# KGGR_UCCv2.net
KiCad netlist of a schematic drawn in EAGLE
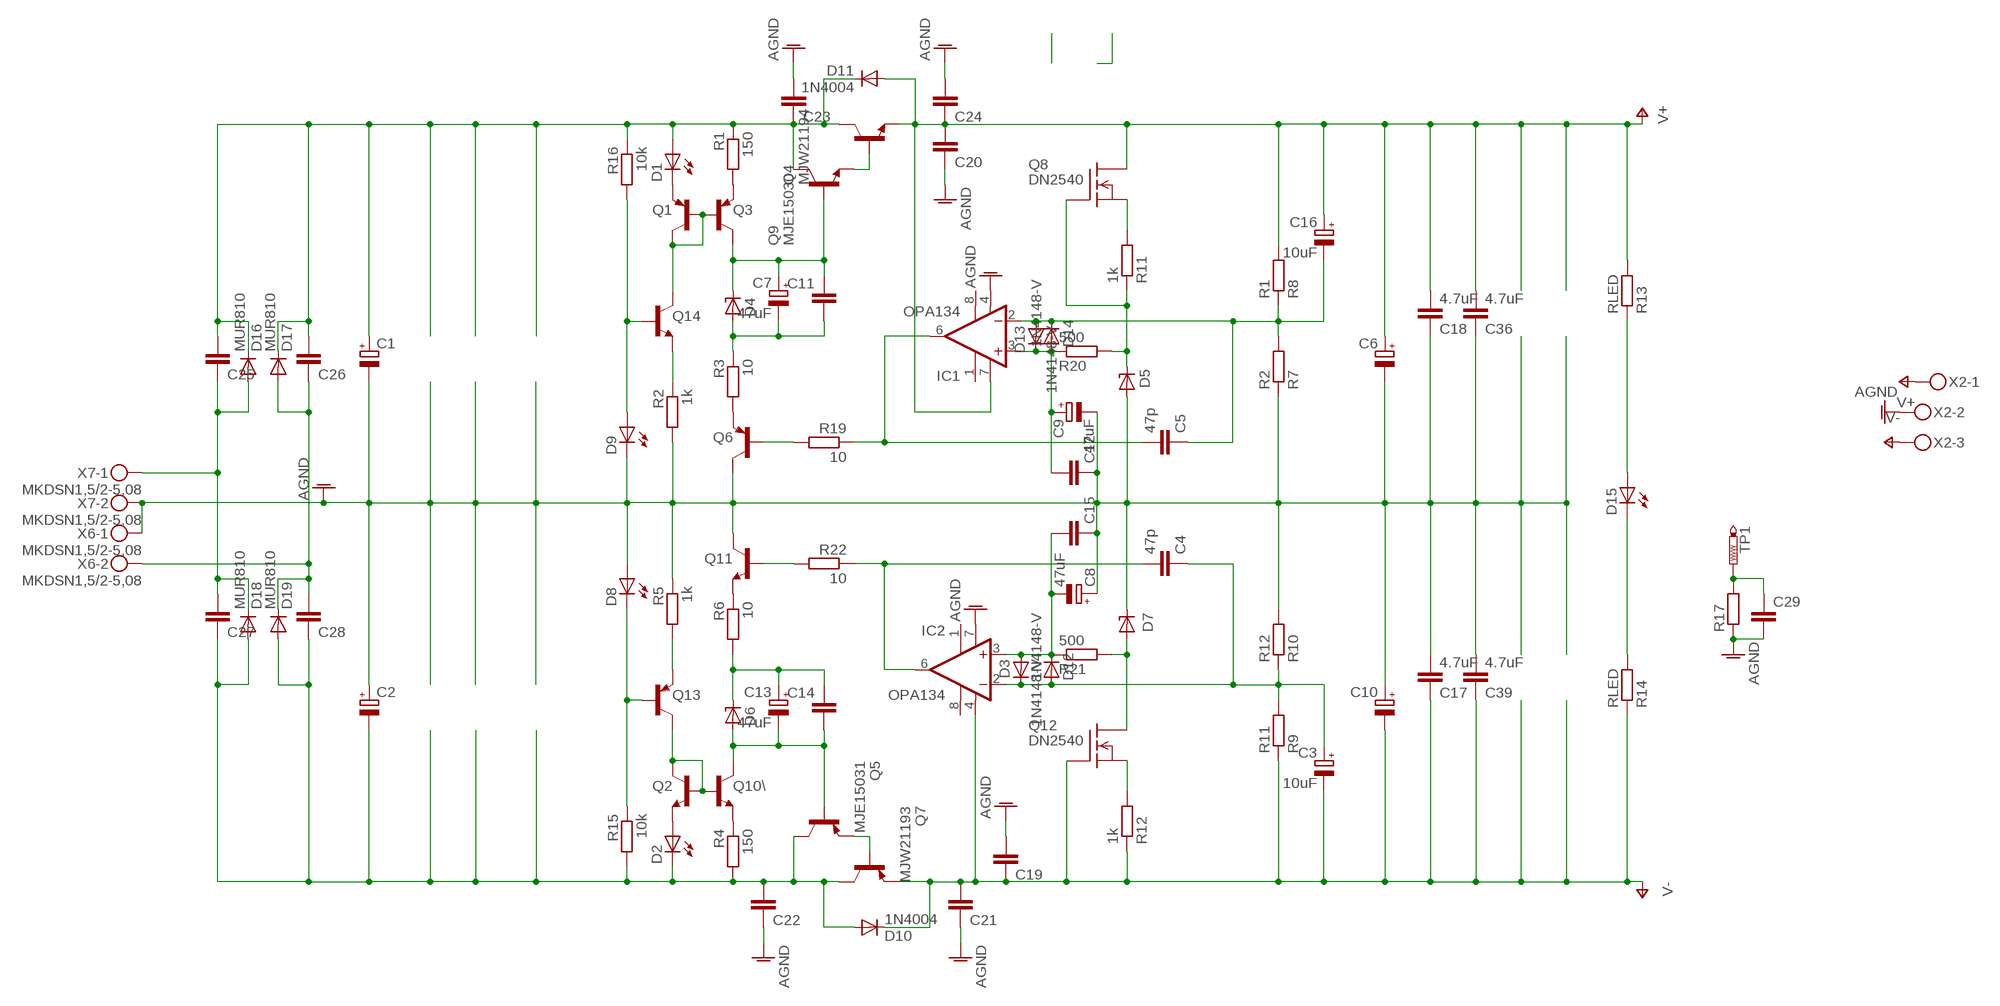
[diagram p0: schematic, sheet 1]

(export (version "E")
  (design (tool "Eeschema 10.0.6"))
  (components
    (comp (ref "C1")
      (value "CPOL-EUE10-30")
      (footprint "eagle-import:EB30D")
      (libsource (lib "eagle-import") (part "CPOL-EUE10-30"))
    )
    (comp (ref "C2")
      (value "CPOL-EUE10-30")
      (footprint "eagle-import:EB30D")
      (libsource (lib "eagle-import") (part "CPOL-EUE10-30"))
    )
    (comp (ref "C3")
      (value "10uF")
      (footprint "eagle-import:SP-CAP-CX")
      (libsource (lib "eagle-import") (part "CPOL-EUSP-CAP-CX"))
    )
    (comp (ref "C4")
      (value "47p")
      (footprint "eagle-import:C1206")
      (libsource (lib "eagle-import") (part "C-EUC1206"))
    )
    (comp (ref "C5")
      (value "47p")
      (footprint "eagle-import:C1206")
      (libsource (lib "eagle-import") (part "C-EUC1206"))
    )
    (comp (ref "C6")
      (value "CPOL-EUE5-13")
      (footprint "eagle-import:E5-13")
      (libsource (lib "eagle-import") (part "CPOL-EUE5-13"))
    )
    (comp (ref "C7")
      (value "47uF")
      (footprint "eagle-import:SP-CAP-CX")
      (libsource (lib "eagle-import") (part "CPOL-EUSP-CAP-CX"))
    )
    (comp (ref "C8")
      (value "47uF")
      (footprint "eagle-import:SP-CAP-CX")
      (libsource (lib "eagle-import") (part "CPOL-EUSP-CAP-CX"))
    )
    (comp (ref "C9")
      (value "47uF")
      (footprint "eagle-import:SP-CAP-CX")
      (libsource (lib "eagle-import") (part "CPOL-EUSP-CAP-CX"))
    )
    (comp (ref "C10")
      (value "CPOL-EUE5-13")
      (footprint "eagle-import:E5-13")
      (libsource (lib "eagle-import") (part "CPOL-EUE5-13"))
    )
    (comp (ref "C11")
      (value "C-EUC1206")
      (footprint "eagle-import:C1206")
      (libsource (lib "eagle-import") (part "C-EUC1206"))
    )
    (comp (ref "C12")
      (value "C-EU050-035X075")
      (footprint "eagle-import:C050-035X075")
      (libsource (lib "eagle-import") (part "C-EU050-035X075"))
    )
    (comp (ref "C13")
      (value "47uF")
      (footprint "eagle-import:SP-CAP-CX")
      (libsource (lib "eagle-import") (part "CPOL-EUSP-CAP-CX"))
    )
    (comp (ref "C14")
      (value "C-EUC1206")
      (footprint "eagle-import:C1206")
      (libsource (lib "eagle-import") (part "C-EUC1206"))
    )
    (comp (ref "C15")
      (value "C-EU050-035X075")
      (footprint "eagle-import:C050-035X075")
      (libsource (lib "eagle-import") (part "C-EU050-035X075"))
    )
    (comp (ref "C16")
      (value "10uF")
      (footprint "eagle-import:SP-CAP-CX")
      (libsource (lib "eagle-import") (part "CPOL-EUSP-CAP-CX"))
    )
    (comp (ref "C17")
      (value "4.7uF")
      (footprint "eagle-import:C1206")
      (libsource (lib "eagle-import") (part "C-EUC1206"))
    )
    (comp (ref "C18")
      (value "4.7uF")
      (footprint "eagle-import:C1206")
      (libsource (lib "eagle-import") (part "C-EUC1206"))
    )
    (comp (ref "C19")
      (value "C-EU050-035X075")
      (footprint "eagle-import:C050-035X075")
      (libsource (lib "eagle-import") (part "C-EU050-035X075"))
    )
    (comp (ref "C20")
      (value "C-EU050-035X075")
      (footprint "eagle-import:C050-035X075")
      (libsource (lib "eagle-import") (part "C-EU050-035X075"))
    )
    (comp (ref "C21")
      (value "C-EU050-035X075")
      (footprint "eagle-import:C050-035X075")
      (libsource (lib "eagle-import") (part "C-EU050-035X075"))
    )
    (comp (ref "C22")
      (value "C-EU050-075X075")
      (footprint "eagle-import:C050-075X075")
      (libsource (lib "eagle-import") (part "C-EU050-075X075"))
    )
    (comp (ref "C23")
      (value "C-EU050-075X075")
      (footprint "eagle-import:C050-075X075")
      (libsource (lib "eagle-import") (part "C-EU050-075X075"))
    )
    (comp (ref "C24")
      (value "C-EU050-035X075")
      (footprint "eagle-import:C050-035X075")
      (libsource (lib "eagle-import") (part "C-EU050-035X075"))
    )
    (comp (ref "C25")
      (value "C-EU050-035X075")
      (footprint "eagle-import:C050-035X075")
      (libsource (lib "eagle-import") (part "C-EU050-035X075"))
    )
    (comp (ref "C26")
      (value "C-EU050-035X075")
      (footprint "eagle-import:C050-035X075")
      (libsource (lib "eagle-import") (part "C-EU050-035X075"))
    )
    (comp (ref "C27")
      (value "C-EU050-035X075")
      (footprint "eagle-import:C050-035X075")
      (libsource (lib "eagle-import") (part "C-EU050-035X075"))
    )
    (comp (ref "C28")
      (value "C-EU050-035X075")
      (footprint "eagle-import:C050-035X075")
      (libsource (lib "eagle-import") (part "C-EU050-035X075"))
    )
    (comp (ref "C29")
      (value "C-EU075-042X103")
      (footprint "eagle-import:C075-042X103")
      (libsource (lib "eagle-import") (part "C-EU075-042X103"))
    )
    (comp (ref "C36")
      (value "4.7uF")
      (footprint "eagle-import:C1206")
      (libsource (lib "eagle-import") (part "C-EUC1206"))
    )
    (comp (ref "C39")
      (value "4.7uF")
      (footprint "eagle-import:C1206")
      (libsource (lib "eagle-import") (part "C-EUC1206"))
    )
    (comp (ref "D1")
      (value "LED5MM")
      (footprint "eagle-import:LED5MM")
      (libsource (lib "eagle-import") (part "LED5MM"))
    )
    (comp (ref "D2")
      (value "LED5MM")
      (footprint "eagle-import:LED5MM")
      (libsource (lib "eagle-import") (part "LED5MM"))
    )
    (comp (ref "D3")
      (value "1N4148-V")
      (footprint "eagle-import:1N4148")
      (libsource (lib "eagle-import") (part "1N4148-V"))
    )
    (comp (ref "D4")
      (value "1N4728")
      (footprint "eagle-import:DO41Z10")
      (libsource (lib "eagle-import") (part "1N4728"))
    )
    (comp (ref "D5")
      (value "LT1021")
      (footprint "eagle-import:DIL08")
      (libsource (lib "eagle-import") (part "LT1021-V"))
    )
    (comp (ref "D6")
      (value "1N4728")
      (footprint "eagle-import:DO41Z10")
      (libsource (lib "eagle-import") (part "1N4728"))
    )
    (comp (ref "D7")
      (value "LT1021")
      (footprint "eagle-import:DIL08")
      (libsource (lib "eagle-import") (part "LT1021-V"))
    )
    (comp (ref "D8")
      (value "LED5MM")
      (footprint "eagle-import:LED5MM")
      (libsource (lib "eagle-import") (part "LED5MM"))
    )
    (comp (ref "D9")
      (value "LED5MM")
      (footprint "eagle-import:LED5MM")
      (libsource (lib "eagle-import") (part "LED5MM"))
    )
    (comp (ref "D10")
      (value "1N4004")
      (footprint "eagle-import:DO41-10")
      (libsource (lib "eagle-import") (part "diode_210_1N4004"))
    )
    (comp (ref "D11")
      (value "1N4004")
      (footprint "eagle-import:DO41-10")
      (libsource (lib "eagle-import") (part "1N4004"))
    )
    (comp (ref "D12")
      (value "1N4148-V")
      (footprint "eagle-import:1N4148")
      (libsource (lib "eagle-import") (part "1N4148-V"))
    )
    (comp (ref "D13")
      (value "1N4148-V")
      (footprint "eagle-import:1N4148")
      (libsource (lib "eagle-import") (part "1N4148-V"))
    )
    (comp (ref "D14")
      (value "1N4148-V")
      (footprint "eagle-import:1N4148")
      (libsource (lib "eagle-import") (part "1N4148-V"))
    )
    (comp (ref "D15")
      (value "LED5MM")
      (footprint "eagle-import:LED5MM")
      (libsource (lib "eagle-import") (part "LED5MM"))
    )
    (comp (ref "D16")
      (value "MUR810")
      (footprint "eagle-import:TO220ACS")
      (libsource (lib "eagle-import") (part "MUR810"))
    )
    (comp (ref "D17")
      (value "MUR810")
      (footprint "eagle-import:TO220ACS")
      (libsource (lib "eagle-import") (part "MUR810"))
    )
    (comp (ref "D18")
      (value "MUR810")
      (footprint "eagle-import:TO220ACS")
      (libsource (lib "eagle-import") (part "MUR810"))
    )
    (comp (ref "D19")
      (value "MUR810")
      (footprint "eagle-import:TO220ACS")
      (libsource (lib "eagle-import") (part "MUR810"))
    )
    (comp (ref "IC1")
      (value "OPA134")
      (footprint "eagle-import:DIL08")
      (fields (field (name "MF") "TEXAS INSTRUMENTS") (field (name "MPN") "OPA134PA"))
      (libsource (lib "eagle-import") (part "OPA134P"))
    )
    (comp (ref "IC2")
      (value "OPA134")
      (footprint "eagle-import:DIL08")
      (fields (field (name "MF") "TEXAS INSTRUMENTS") (field (name "MPN") "OPA134PA"))
      (libsource (lib "eagle-import") (part "OPA134P"))
    )
    (comp (ref "Q1")
      (value "MPSA92-PNP-TO92-EBC")
      (footprint "eagle-import:TO92-EBC")
      (libsource (lib "eagle-import") (part "-PNP-TO92-EBCMPSA92"))
    )
    (comp (ref "Q2")
      (value "MPSA42-NPN-TO92-EBC")
      (footprint "eagle-import:TO92-EBC")
      (libsource (lib "eagle-import") (part "-NPN-TO92-EBCMPSA42"))
    )
    (comp (ref "Q3")
      (value "MPSA92-PNP-TO92-EBC")
      (footprint "eagle-import:TO92-EBC")
      (libsource (lib "eagle-import") (part "-PNP-TO92-EBCMPSA92"))
    )
    (comp (ref "Q4")
      (value "MJW21194")
      (footprint "eagle-import:TO-264")
      (libsource (lib "eagle-import") (part "MJL4281"))
    )
    (comp (ref "Q5")
      (value "MJE15031")
      (footprint "eagle-import:TO220KG")
      (libsource (lib "eagle-import") (part "MJE15031"))
    )
    (comp (ref "Q6")
      (value "MPSA92-PNP-TO92-EBC")
      (footprint "eagle-import:TO92-EBC")
      (libsource (lib "eagle-import") (part "-PNP-TO92-EBCMPSA92"))
    )
    (comp (ref "Q7")
      (value "MJW21193")
      (footprint "eagle-import:TO-264")
      (libsource (lib "eagle-import") (part "MJL4302"))
    )
    (comp (ref "Q8")
      (value "DN2540")
      (footprint "eagle-import:TO92-")
      (libsource (lib "eagle-import") (part "2N7000TO92"))
    )
    (comp (ref "Q9")
      (value "MJE15030")
      (footprint "eagle-import:TO220KG")
      (libsource (lib "eagle-import") (part "MJE15030"))
    )
    (comp (ref "Q10\\")
      (value "MPSA42-NPN-TO92-EBC")
      (footprint "eagle-import:TO92-EBC")
      (libsource (lib "eagle-import") (part "-NPN-TO92-EBCMPSA42"))
    )
    (comp (ref "Q11")
      (value "MPSA42-NPN-TO92-EBC")
      (footprint "eagle-import:TO92-EBC")
      (libsource (lib "eagle-import") (part "-NPN-TO92-EBCMPSA42"))
    )
    (comp (ref "Q12")
      (value "DN2540")
      (footprint "eagle-import:TO92-")
      (libsource (lib "eagle-import") (part "2N7000TO92"))
    )
    (comp (ref "Q13")
      (value "MPSA92-PNP-TO92-EBC")
      (footprint "eagle-import:TO92-EBC")
      (libsource (lib "eagle-import") (part "-PNP-TO92-EBCMPSA92"))
    )
    (comp (ref "Q14")
      (value "MPSA42-NPN-TO92-EBC")
      (footprint "eagle-import:TO92-EBC")
      (libsource (lib "eagle-import") (part "-NPN-TO92-EBCMPSA42"))
    )
    (comp (ref "R1")
      (value "150")
      (footprint "eagle-import:0207_2V")
      (libsource (lib "eagle-import") (part "R-EU_0207/2V"))
    )
    (comp (ref "R2")
      (value "1k")
      (footprint "eagle-import:0207_2V")
      (libsource (lib "eagle-import") (part "R-EU_0207/2V"))
    )
    (comp (ref "R3")
      (value "10")
      (footprint "eagle-import:0207_2V")
      (libsource (lib "eagle-import") (part "R-EU_0207/2V"))
    )
    (comp (ref "R4")
      (value "150")
      (footprint "eagle-import:0207_2V")
      (libsource (lib "eagle-import") (part "R-EU_0207/2V"))
    )
    (comp (ref "R5")
      (value "1k")
      (footprint "eagle-import:0207_2V")
      (libsource (lib "eagle-import") (part "R-EU_0207/2V"))
    )
    (comp (ref "R6")
      (value "10")
      (footprint "eagle-import:0207_2V")
      (libsource (lib "eagle-import") (part "R-EU_0207/2V"))
    )
    (comp (ref "R7")
      (value "R2")
      (footprint "eagle-import:0207_2V")
      (libsource (lib "eagle-import") (part "R-EU_0207/2V"))
    )
    (comp (ref "R8")
      (value "R1")
      (footprint "eagle-import:0207_2V")
      (libsource (lib "eagle-import") (part "R-EU_0207/2V"))
    )
    (comp (ref "R9")
      (value "R11")
      (footprint "eagle-import:0207_2V")
      (libsource (lib "eagle-import") (part "R-EU_0207/2V"))
    )
    (comp (ref "R10")
      (value "R12")
      (footprint "eagle-import:0207_2V")
      (libsource (lib "eagle-import") (part "R-EU_0207/2V"))
    )
    (comp (ref "R11")
      (value "1k")
      (footprint "eagle-import:0207_2V")
      (libsource (lib "eagle-import") (part "R-EU_0207/2V"))
    )
    (comp (ref "R12")
      (value "1k")
      (footprint "eagle-import:0207_2V")
      (libsource (lib "eagle-import") (part "R-EU_0207/2V"))
    )
    (comp (ref "R13")
      (value "RLED")
      (footprint "eagle-import:0207_2V")
      (libsource (lib "eagle-import") (part "R-EU_0207/2V"))
    )
    (comp (ref "R14")
      (value "RLED")
      (footprint "eagle-import:0207_2V")
      (libsource (lib "eagle-import") (part "R-EU_0207/2V"))
    )
    (comp (ref "R15")
      (value "10k")
      (footprint "eagle-import:0207_2V")
      (libsource (lib "eagle-import") (part "R-EU_0207/2V"))
    )
    (comp (ref "R16")
      (value "10k")
      (footprint "eagle-import:0207_2V")
      (libsource (lib "eagle-import") (part "R-EU_0207/2V"))
    )
    (comp (ref "R17")
      (value "R-EU_0207/10")
      (footprint "eagle-import:0207_10")
      (libsource (lib "eagle-import") (part "R-EU_0207/10"))
    )
    (comp (ref "R19")
      (value "10")
      (footprint "eagle-import:0207_2V")
      (libsource (lib "eagle-import") (part "R-EU_0207/2V"))
    )
    (comp (ref "R20")
      (value "500")
      (footprint "eagle-import:0207_2V")
      (libsource (lib "eagle-import") (part "R-EU_0207/2V"))
    )
    (comp (ref "R21")
      (value "500")
      (footprint "eagle-import:0207_2V")
      (libsource (lib "eagle-import") (part "R-EU_0207/2V"))
    )
    (comp (ref "R22")
      (value "10")
      (footprint "eagle-import:0207_2V")
      (libsource (lib "eagle-import") (part "R-EU_0207/2V"))
    )
    (comp (ref "TP1")
      (value "PTR1PAD1-20")
      (footprint "eagle-import:P1-20")
      (libsource (lib "eagle-import") (part "PTR1PAD1-20"))
    )
    (comp (ref "X2")
      (value "MKDSN1,5/3-5,08")
      (footprint "eagle-import:MKDSN1,5_3-5,08")
      (libsource (lib "eagle-import") (part "MKDSN1,5/3-5,08"))
    )
    (comp (ref "X6")
      (value "MKDSN1,5/2-5,08")
      (footprint "eagle-import:MKDSN1,5_2-5,08")
      (libsource (lib "eagle-import") (part "MKDSN1,5/2-5,08"))
    )
    (comp (ref "X7")
      (value "MKDSN1,5/2-5,08")
      (footprint "eagle-import:MKDSN1,5_2-5,08")
      (libsource (lib "eagle-import") (part "MKDSN1,5/2-5,08"))
    )
  )
  (nets
    (net (code "1") (name "AGND") (class "Default")
      (node (ref "C1") (pin "-") (pinfunction "-_-") (pintype "passive"))
      (node (ref "C10") (pin "+") (pinfunction "+_+") (pintype "passive"))
      (node (ref "C12") (pin "1") (pinfunction "1_1") (pintype "passive"))
      (node (ref "C15") (pin "1") (pinfunction "1_1") (pintype "passive"))
      (node (ref "C17") (pin "2") (pinfunction "2_2") (pintype "passive"))
      (node (ref "C18") (pin "1") (pinfunction "1_1") (pintype "passive"))
      (node (ref "C19") (pin "2") (pinfunction "2_2") (pintype "passive"))
      (node (ref "C2") (pin "+") (pinfunction "+_+") (pintype "passive"))
      (node (ref "C20") (pin "1") (pinfunction "1_1") (pintype "passive"))
      (node (ref "C21") (pin "1") (pinfunction "1_1") (pintype "passive"))
      (node (ref "C22") (pin "1") (pinfunction "1_1") (pintype "passive"))
      (node (ref "C23") (pin "2") (pinfunction "2_2") (pintype "passive"))
      (node (ref "C24") (pin "2") (pinfunction "2_2") (pintype "passive"))
      (node (ref "C29") (pin "2") (pinfunction "2_2") (pintype "passive"))
      (node (ref "C36") (pin "1") (pinfunction "1_1") (pintype "passive"))
      (node (ref "C39") (pin "2") (pinfunction "2_2") (pintype "passive"))
      (node (ref "C6") (pin "-") (pinfunction "-_-") (pintype "passive"))
      (node (ref "C8") (pin "+") (pinfunction "+_+") (pintype "passive"))
      (node (ref "C9") (pin "-") (pinfunction "-_-") (pintype "passive"))
      (node (ref "D5") (pin "4") (pinfunction "GND_4") (pintype "passive"))
      (node (ref "D7") (pin "6") (pinfunction "OUT_6") (pintype "passive"))
      (node (ref "D8") (pin "A") (pinfunction "A_A") (pintype "passive"))
      (node (ref "D9") (pin "K") (pinfunction "C_K") (pintype "passive"))
      (node (ref "IC1") (pin "4") (pinfunction "V-_4") (pintype "power_in"))
      (node (ref "IC2") (pin "7") (pinfunction "V+_7") (pintype "power_in"))
      (node (ref "Q11") (pin "C") (pinfunction "C_C") (pintype "passive"))
      (node (ref "Q6") (pin "C") (pinfunction "C_C") (pintype "passive"))
      (node (ref "R10") (pin "2") (pinfunction "2_2") (pintype "passive"))
      (node (ref "R17") (pin "1") (pinfunction "1_1") (pintype "passive"))
      (node (ref "R2") (pin "2") (pinfunction "2_2") (pintype "passive"))
      (node (ref "R5") (pin "1") (pinfunction "1_1") (pintype "passive"))
      (node (ref "R7") (pin "1") (pinfunction "1_1") (pintype "passive"))
      (node (ref "X2") (pin "2") (pinfunction "KL_2") (pintype "passive"))
      (node (ref "X6") (pin "1") (pinfunction "KL_1") (pintype "passive"))
      (node (ref "X7") (pin "2") (pinfunction "KL_2") (pintype "passive"))
    )
    (net (code "2") (name "Net-(C11-Pad2)") (class "Default")
      (node (ref "C11") (pin "2") (pinfunction "2_2") (pintype "passive"))
      (node (ref "C7") (pin "-") (pinfunction "-_-") (pintype "passive"))
      (node (ref "D4") (pin "A") (pinfunction "A_A") (pintype "passive"))
      (node (ref "R3") (pin "1") (pinfunction "1_1") (pintype "passive"))
    )
    (net (code "3") (name "Net-(C13-Pad+)") (class "Default")
      (node (ref "C13") (pin "+") (pinfunction "+_+") (pintype "passive"))
      (node (ref "C14") (pin "1") (pinfunction "1_1") (pintype "passive"))
      (node (ref "D6") (pin "C") (pinfunction "C_C") (pintype "passive"))
      (node (ref "R6") (pin "2") (pinfunction "2_2") (pintype "passive"))
    )
    (net (code "4") (name "Net-(C29-Pad1)") (class "Default")
      (node (ref "C29") (pin "1") (pinfunction "1_1") (pintype "passive"))
      (node (ref "R17") (pin "2") (pinfunction "2_2") (pintype "passive"))
      (node (ref "TP1") (pin "TP") (pinfunction "TP_TP") (pintype "input"))
    )
    (net (code "5") (name "Net-(D1-C)") (class "Default")
      (node (ref "D1") (pin "K") (pinfunction "C_K") (pintype "passive"))
      (node (ref "Q1") (pin "E") (pinfunction "E_E") (pintype "passive"))
    )
    (net (code "6") (name "Net-(D2-C)") (class "Default")
      (node (ref "C2") (pin "-") (pinfunction "-_-") (pintype "passive"))
      (node (ref "C22") (pin "2") (pinfunction "2_2") (pintype "passive"))
      (node (ref "C27") (pin "1") (pinfunction "1_1") (pintype "passive"))
      (node (ref "C28") (pin "1") (pinfunction "1_1") (pintype "passive"))
      (node (ref "D10") (pin "A") (pinfunction "A_A") (pintype "passive"))
      (node (ref "D18") (pin "A") (pinfunction "A_A") (pintype "passive"))
      (node (ref "D19") (pin "A") (pinfunction "A_A") (pintype "passive"))
      (node (ref "D2") (pin "K") (pinfunction "C_K") (pintype "passive"))
      (node (ref "Q5") (pin "2") (pinfunction "C_2") (pintype "passive"))
      (node (ref "Q7") (pin "C") (pinfunction "C_C") (pintype "passive"))
      (node (ref "R15") (pin "2") (pinfunction "2_2") (pintype "passive"))
      (node (ref "R4") (pin "2") (pinfunction "2_2") (pintype "passive"))
    )
    (net (code "7") (name "Net-(D2-PadA)") (class "Default")
      (node (ref "D2") (pin "A") (pinfunction "A_A") (pintype "passive"))
      (node (ref "Q2") (pin "E") (pinfunction "E_E") (pintype "passive"))
    )
    (net (code "8") (name "Net-(D5-OUT)") (class "Default")
      (node (ref "D5") (pin "6") (pinfunction "OUT_6") (pintype "passive"))
      (node (ref "Q8") (pin "2") (pinfunction "G_2") (pintype "passive"))
      (node (ref "R11") (pin "1") (pinfunction "1_1") (pintype "passive"))
      (node (ref "R20") (pin "2") (pinfunction "2_2") (pintype "passive"))
    )
    (net (code "9") (name "Net-(D7-GND)") (class "Default")
      (node (ref "D7") (pin "4") (pinfunction "GND_4") (pintype "passive"))
      (node (ref "Q12") (pin "1") (pinfunction "D_1") (pintype "passive"))
      (node (ref "R21") (pin "2") (pinfunction "2_2") (pintype "passive"))
    )
    (net (code "10") (name "Net-(D8-C)") (class "Default")
      (node (ref "D8") (pin "K") (pinfunction "C_K") (pintype "passive"))
      (node (ref "Q13") (pin "B") (pinfunction "B_B") (pintype "passive"))
      (node (ref "R15") (pin "1") (pinfunction "1_1") (pintype "passive"))
    )
    (net (code "11") (name "Net-(D9-PadA)") (class "Default")
      (node (ref "D9") (pin "A") (pinfunction "A_A") (pintype "passive"))
      (node (ref "Q14") (pin "B") (pinfunction "B_B") (pintype "passive"))
      (node (ref "R16") (pin "2") (pinfunction "2_2") (pintype "passive"))
    )
    (net (code "12") (name "Net-(D15-C)") (class "Default")
      (node (ref "D15") (pin "K") (pinfunction "C_K") (pintype "passive"))
      (node (ref "R14") (pin "2") (pinfunction "2_2") (pintype "passive"))
    )
    (net (code "13") (name "Net-(D15-PadA)") (class "Default")
      (node (ref "D15") (pin "A") (pinfunction "A_A") (pintype "passive"))
      (node (ref "R13") (pin "1") (pinfunction "1_1") (pintype "passive"))
    )
    (net (code "14") (name "Net-(IC1-+IN)") (class "Default")
      (node (ref "C12") (pin "2") (pinfunction "2_2") (pintype "passive"))
      (node (ref "C9") (pin "+") (pinfunction "+_+") (pintype "passive"))
      (node (ref "D13") (pin "C") (pinfunction "C_C") (pintype "passive"))
      (node (ref "D14") (pin "A") (pinfunction "A_A") (pintype "passive"))
      (node (ref "IC1") (pin "3") (pinfunction "+IN_3") (pintype "input"))
      (node (ref "R20") (pin "1") (pinfunction "1_1") (pintype "passive"))
    )
    (net (code "15") (name "Net-(IC1--IN)") (class "Default")
      (node (ref "C16") (pin "-") (pinfunction "-_-") (pintype "passive"))
      (node (ref "C5") (pin "1") (pinfunction "1_1") (pintype "passive"))
      (node (ref "D13") (pin "A") (pinfunction "A_A") (pintype "passive"))
      (node (ref "D14") (pin "C") (pinfunction "C_C") (pintype "passive"))
      (node (ref "IC1") (pin "2") (pinfunction "-IN_2") (pintype "input"))
      (node (ref "R7") (pin "2") (pinfunction "2_2") (pintype "passive"))
      (node (ref "R8") (pin "1") (pinfunction "1_1") (pintype "passive"))
    )
    (net (code "16") (name "Net-(IC1-OUT)") (class "Default")
      (node (ref "C5") (pin "2") (pinfunction "2_2") (pintype "passive"))
      (node (ref "IC1") (pin "6") (pinfunction "OUT_6") (pintype "output"))
      (node (ref "R19") (pin "1") (pinfunction "1_1") (pintype "passive"))
    )
    (net (code "17") (name "Net-(IC2-+IN)") (class "Default")
      (node (ref "C15") (pin "2") (pinfunction "2_2") (pintype "passive"))
      (node (ref "C8") (pin "-") (pinfunction "-_-") (pintype "passive"))
      (node (ref "D12") (pin "C") (pinfunction "C_C") (pintype "passive"))
      (node (ref "D3") (pin "A") (pinfunction "A_A") (pintype "passive"))
      (node (ref "IC2") (pin "3") (pinfunction "+IN_3") (pintype "input"))
      (node (ref "R21") (pin "1") (pinfunction "1_1") (pintype "passive"))
    )
    (net (code "18") (name "Net-(IC2--IN)") (class "Default")
      (node (ref "C3") (pin "+") (pinfunction "+_+") (pintype "passive"))
      (node (ref "C4") (pin "1") (pinfunction "1_1") (pintype "passive"))
      (node (ref "D12") (pin "A") (pinfunction "A_A") (pintype "passive"))
      (node (ref "D3") (pin "C") (pinfunction "C_C") (pintype "passive"))
      (node (ref "IC2") (pin "2") (pinfunction "-IN_2") (pintype "input"))
      (node (ref "R10") (pin "1") (pinfunction "1_1") (pintype "passive"))
      (node (ref "R9") (pin "2") (pinfunction "2_2") (pintype "passive"))
    )
    (net (code "19") (name "Net-(IC2-OUT)") (class "Default")
      (node (ref "C4") (pin "2") (pinfunction "2_2") (pintype "passive"))
      (node (ref "IC2") (pin "6") (pinfunction "OUT_6") (pintype "output"))
      (node (ref "R22") (pin "1") (pinfunction "1_1") (pintype "passive"))
    )
    (net (code "20") (name "Net-(Q1-PadB)") (class "Default")
      (node (ref "Q1") (pin "B") (pinfunction "B_B") (pintype "passive"))
      (node (ref "Q1") (pin "C") (pinfunction "C_C") (pintype "passive"))
      (node (ref "Q14") (pin "C") (pinfunction "C_C") (pintype "passive"))
      (node (ref "Q3") (pin "B") (pinfunction "B_B") (pintype "passive"))
    )
    (net (code "21") (name "Net-(Q3-PadE)") (class "Default")
      (node (ref "Q3") (pin "E") (pinfunction "E_E") (pintype "passive"))
      (node (ref "R1") (pin "2") (pinfunction "2_2") (pintype "passive"))
    )
    (net (code "22") (name "Net-(Q5-B)") (class "Default")
      (node (ref "C13") (pin "-") (pinfunction "-_-") (pintype "passive"))
      (node (ref "C14") (pin "2") (pinfunction "2_2") (pintype "passive"))
      (node (ref "D6") (pin "A") (pinfunction "A_A") (pintype "passive"))
      (node (ref "Q10\\") (pin "C") (pinfunction "C_C") (pintype "passive"))
      (node (ref "Q5") (pin "1") (pinfunction "B_1") (pintype "passive"))
    )
    (net (code "23") (name "Net-(Q5-E)") (class "Default")
      (node (ref "Q5") (pin "3") (pinfunction "E_3") (pintype "passive"))
      (node (ref "Q7") (pin "B") (pinfunction "B_B") (pintype "passive"))
    )
    (net (code "24") (name "Net-(Q6-PadB)") (class "Default")
      (node (ref "Q6") (pin "B") (pinfunction "B_B") (pintype "passive"))
      (node (ref "R19") (pin "2") (pinfunction "2_2") (pintype "passive"))
    )
    (net (code "25") (name "Net-(Q6-PadE)") (class "Default")
      (node (ref "Q6") (pin "E") (pinfunction "E_E") (pintype "passive"))
      (node (ref "R3") (pin "2") (pinfunction "2_2") (pintype "passive"))
    )
    (net (code "26") (name "Net-(Q8-S)") (class "Default")
      (node (ref "Q8") (pin "3") (pinfunction "S_3") (pintype "passive"))
      (node (ref "R11") (pin "2") (pinfunction "2_2") (pintype "passive"))
    )
    (net (code "27") (name "Net-(Q9-B)") (class "Default")
      (node (ref "C11") (pin "1") (pinfunction "1_1") (pintype "passive"))
      (node (ref "C7") (pin "+") (pinfunction "+_+") (pintype "passive"))
      (node (ref "D4") (pin "C") (pinfunction "C_C") (pintype "passive"))
      (node (ref "Q3") (pin "C") (pinfunction "C_C") (pintype "passive"))
      (node (ref "Q9") (pin "1") (pinfunction "B_1") (pintype "passive"))
    )
    (net (code "28") (name "Net-(Q9-C)") (class "Default")
      (node (ref "C1") (pin "+") (pinfunction "+_+") (pintype "passive"))
      (node (ref "C23") (pin "1") (pinfunction "1_1") (pintype "passive"))
      (node (ref "C25") (pin "2") (pinfunction "2_2") (pintype "passive"))
      (node (ref "C26") (pin "2") (pinfunction "2_2") (pintype "passive"))
      (node (ref "D1") (pin "A") (pinfunction "A_A") (pintype "passive"))
      (node (ref "D11") (pin "C") (pinfunction "C_C") (pintype "passive"))
      (node (ref "D16") (pin "C") (pinfunction "C_C") (pintype "passive"))
      (node (ref "D17") (pin "C") (pinfunction "C_C") (pintype "passive"))
      (node (ref "Q4") (pin "C") (pinfunction "C_C") (pintype "passive"))
      (node (ref "Q9") (pin "2") (pinfunction "C_2") (pintype "passive"))
      (node (ref "R1") (pin "1") (pinfunction "1_1") (pintype "passive"))
      (node (ref "R16") (pin "1") (pinfunction "1_1") (pintype "passive"))
    )
    (net (code "29") (name "Net-(Q9-E)") (class "Default")
      (node (ref "Q4") (pin "B") (pinfunction "B_B") (pintype "passive"))
      (node (ref "Q9") (pin "3") (pinfunction "E_3") (pintype "passive"))
    )
    (net (code "30") (name "Net-(Q10\\-PadB)") (class "Default")
      (node (ref "Q10\\") (pin "B") (pinfunction "B_B") (pintype "passive"))
      (node (ref "Q13") (pin "C") (pinfunction "C_C") (pintype "passive"))
      (node (ref "Q2") (pin "B") (pinfunction "B_B") (pintype "passive"))
      (node (ref "Q2") (pin "C") (pinfunction "C_C") (pintype "passive"))
    )
    (net (code "31") (name "Net-(Q10\\-PadE)") (class "Default")
      (node (ref "Q10\\") (pin "E") (pinfunction "E_E") (pintype "passive"))
      (node (ref "R4") (pin "1") (pinfunction "1_1") (pintype "passive"))
    )
    (net (code "32") (name "Net-(Q11-PadB)") (class "Default")
      (node (ref "Q11") (pin "B") (pinfunction "B_B") (pintype "passive"))
      (node (ref "R22") (pin "2") (pinfunction "2_2") (pintype "passive"))
    )
    (net (code "33") (name "Net-(Q11-PadE)") (class "Default")
      (node (ref "Q11") (pin "E") (pinfunction "E_E") (pintype "passive"))
      (node (ref "R6") (pin "1") (pinfunction "1_1") (pintype "passive"))
    )
    (net (code "34") (name "Net-(Q12-S)") (class "Default")
      (node (ref "Q12") (pin "3") (pinfunction "S_3") (pintype "passive"))
      (node (ref "R12") (pin "2") (pinfunction "2_2") (pintype "passive"))
    )
    (net (code "35") (name "Net-(Q13-PadE)") (class "Default")
      (node (ref "Q13") (pin "E") (pinfunction "E_E") (pintype "passive"))
      (node (ref "R5") (pin "2") (pinfunction "2_2") (pintype "passive"))
    )
    (net (code "36") (name "Net-(Q14-PadE)") (class "Default")
      (node (ref "Q14") (pin "E") (pinfunction "E_E") (pintype "passive"))
      (node (ref "R2") (pin "1") (pinfunction "1_1") (pintype "passive"))
    )
    (net (code "37") (name "Net-(X6B-KL)") (class "Default")
      (node (ref "C26") (pin "1") (pinfunction "1_1") (pintype "passive"))
      (node (ref "C28") (pin "2") (pinfunction "2_2") (pintype "passive"))
      (node (ref "D17") (pin "A") (pinfunction "A_A") (pintype "passive"))
      (node (ref "D19") (pin "C") (pinfunction "C_C") (pintype "passive"))
      (node (ref "X6") (pin "2") (pinfunction "KL_2") (pintype "passive"))
    )
    (net (code "38") (name "Net-(X7A-KL)") (class "Default")
      (node (ref "C25") (pin "1") (pinfunction "1_1") (pintype "passive"))
      (node (ref "C27") (pin "2") (pinfunction "2_2") (pintype "passive"))
      (node (ref "D16") (pin "A") (pinfunction "A_A") (pintype "passive"))
      (node (ref "D18") (pin "C") (pinfunction "C_C") (pintype "passive"))
      (node (ref "X7") (pin "1") (pinfunction "KL_1") (pintype "passive"))
    )
    (net (code "39") (name "V+") (class "Default")
      (node (ref "C16") (pin "+") (pinfunction "+_+") (pintype "passive"))
      (node (ref "C18") (pin "2") (pinfunction "2_2") (pintype "passive"))
      (node (ref "C20") (pin "2") (pinfunction "2_2") (pintype "passive"))
      (node (ref "C24") (pin "1") (pinfunction "1_1") (pintype "passive"))
      (node (ref "C36") (pin "2") (pinfunction "2_2") (pintype "passive"))
      (node (ref "C6") (pin "+") (pinfunction "+_+") (pintype "passive"))
      (node (ref "D11") (pin "A") (pinfunction "A_A") (pintype "passive"))
      (node (ref "IC1") (pin "7") (pinfunction "V+_7") (pintype "power_in"))
      (node (ref "Q4") (pin "E") (pinfunction "E_E") (pintype "passive"))
      (node (ref "Q8") (pin "1") (pinfunction "D_1") (pintype "passive"))
      (node (ref "R13") (pin "2") (pinfunction "2_2") (pintype "passive"))
      (node (ref "R8") (pin "2") (pinfunction "2_2") (pintype "passive"))
      (node (ref "X2") (pin "1") (pinfunction "KL_1") (pintype "passive"))
    )
    (net (code "40") (name "V-") (class "Default")
      (node (ref "C10") (pin "-") (pinfunction "-_-") (pintype "passive"))
      (node (ref "C17") (pin "1") (pinfunction "1_1") (pintype "passive"))
      (node (ref "C19") (pin "1") (pinfunction "1_1") (pintype "passive"))
      (node (ref "C21") (pin "2") (pinfunction "2_2") (pintype "passive"))
      (node (ref "C3") (pin "-") (pinfunction "-_-") (pintype "passive"))
      (node (ref "C39") (pin "1") (pinfunction "1_1") (pintype "passive"))
      (node (ref "D10") (pin "C") (pinfunction "C_C") (pintype "passive"))
      (node (ref "IC2") (pin "4") (pinfunction "V-_4") (pintype "power_in"))
      (node (ref "Q12") (pin "2") (pinfunction "G_2") (pintype "passive"))
      (node (ref "Q7") (pin "E") (pinfunction "E_E") (pintype "passive"))
      (node (ref "R12") (pin "1") (pinfunction "1_1") (pintype "passive"))
      (node (ref "R14") (pin "1") (pinfunction "1_1") (pintype "passive"))
      (node (ref "R9") (pin "1") (pinfunction "1_1") (pintype "passive"))
      (node (ref "X2") (pin "3") (pinfunction "KL_3") (pintype "passive"))
    )
    (net (code "41") (name "unconnected-(IC1-TRIM1-Pad1)") (class "Default")
      (node (ref "IC1") (pin "1") (pinfunction "TRIM1_1") (pintype "passive"))
    )
    (net (code "42") (name "unconnected-(IC1-TRIM2-Pad8)") (class "Default")
      (node (ref "IC1") (pin "8") (pinfunction "TRIM2_8") (pintype "passive"))
    )
    (net (code "43") (name "unconnected-(IC2-TRIM1-Pad1)") (class "Default")
      (node (ref "IC2") (pin "1") (pinfunction "TRIM1_1") (pintype "passive"))
    )
    (net (code "44") (name "unconnected-(IC2-TRIM2-Pad8)") (class "Default")
      (node (ref "IC2") (pin "8") (pinfunction "TRIM2_8") (pintype "passive"))
    )
  )
)
